# Schematics.net
KiCad netlist of a schematic drawn in Altium Designer
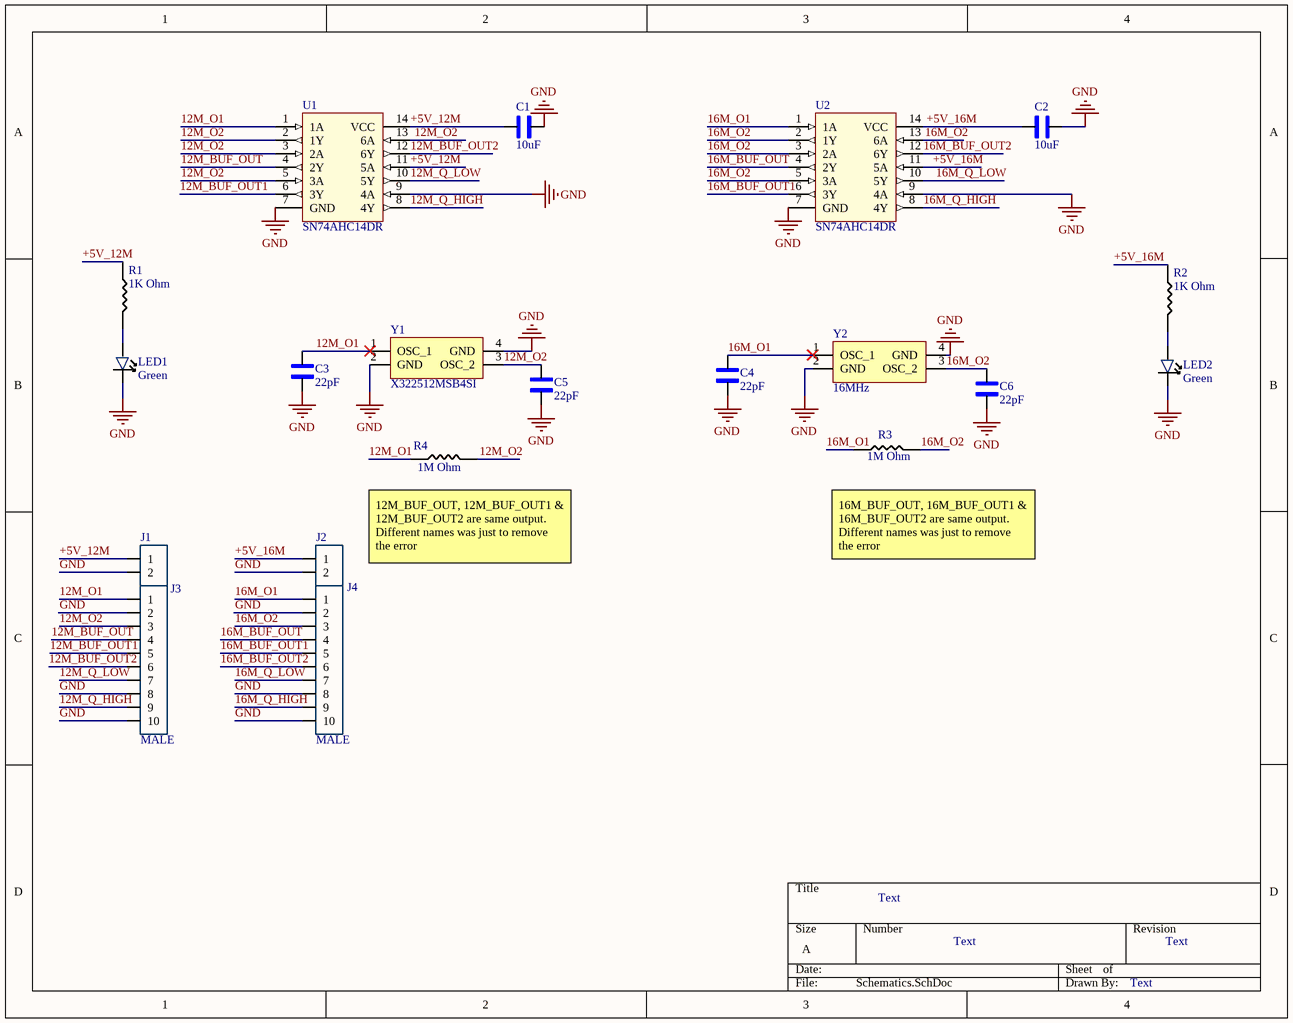
[diagram p0: Schematics.SchDoc]

(export (version "E")
  (design (tool "Eeschema 10.0.6"))
  (components
    (comp (ref "C1")
      (value "10uF")
      (footprint "0402_Passive_Capacitor")
      (description "10uF ±20% 6.3V X5R 0402 Multilayer Ceramic Capacitors MLCC - SMD/SMT RoHS")
      (fields (field (name "MFR PART #") "CL05A106MQ5NUNC") (field (name "LCSC PART#") "C15525"))
      (libsource (lib "ECEN5730Lib_JLC_2022_10") (part "C_10uF_0402"))
    )
    (comp (ref "C2")
      (value "10uF")
      (footprint "0402_Passive_Capacitor")
      (description "10uF ±20% 6.3V X5R 0402 Multilayer Ceramic Capacitors MLCC - SMD/SMT RoHS")
      (fields (field (name "MFR PART #") "CL05A106MQ5NUNC") (field (name "LCSC PART#") "C15525"))
      (libsource (lib "ECEN5730Lib_JLC_2022_10") (part "C_10uF_0402"))
    )
    (comp (ref "C3")
      (value "22pF")
      (footprint "0402_Passive_Capacitor")
      (description "MULTILAYER CERAMIC CAPACITORS MLCC - SMD/SMT 22PF 50V 0402 ROHS")
      (fields (field (name "MFR PART #") "0402CG220J500NT") (field (name "LCSC PART#") "C1555"))
      (libsource (lib "ECEN5730Lib_JLC_2022_10") (part "C_22pF_0402"))
    )
    (comp (ref "C4")
      (value "22pF")
      (footprint "0402_Passive_Capacitor")
      (description "MULTILAYER CERAMIC CAPACITORS MLCC - SMD/SMT 22PF 50V 0402 ROHS")
      (fields (field (name "MFR PART #") "0402CG220J500NT") (field (name "LCSC PART#") "C1555"))
      (libsource (lib "ECEN5730Lib_JLC_2022_10") (part "C_22pF_0402"))
    )
    (comp (ref "C5")
      (value "22pF")
      (footprint "0402_Passive_Capacitor")
      (description "MULTILAYER CERAMIC CAPACITORS MLCC - SMD/SMT 22PF 50V 0402 ROHS")
      (fields (field (name "MFR PART #") "0402CG220J500NT") (field (name "LCSC PART#") "C1555"))
      (libsource (lib "ECEN5730Lib_JLC_2022_10") (part "C_22pF_0402"))
    )
    (comp (ref "C6")
      (value "22pF")
      (footprint "0402_Passive_Capacitor")
      (description "MULTILAYER CERAMIC CAPACITORS MLCC - SMD/SMT 22PF 50V 0402 ROHS")
      (fields (field (name "MFR PART #") "0402CG220J500NT") (field (name "LCSC PART#") "C1555"))
      (libsource (lib "ECEN5730Lib_JLC_2022_10") (part "C_22pF_0402"))
    )
    (comp (ref "J1")
      (value "2 PIN")
      (footprint "2_PIN_100MIL")
      (description "2.54mm Straight 2 1 Header，Breakaway Through Hole,P=2.54mm Pin Header & Female Header ROHS")
      (fields (field (name "LCSC PART#") "C124375") (field (name "MFR PART #") "B-2100S02P-A110"))
      (libsource (lib "ECEN5730Lib_JLC_2022_10") (part "J_2_PIN_HEADER"))
    )
    (comp (ref "J2")
      (value "2 PIN")
      (footprint "2_PIN_100MIL")
      (description "2.54mm Straight 2 1 Header，Breakaway Through Hole,P=2.54mm Pin Header & Female Header ROHS")
      (fields (field (name "LCSC PART#") "C124375") (field (name "MFR PART #") "B-2100S02P-A110"))
      (libsource (lib "ECEN5730Lib_JLC_2022_10") (part "J_2_PIN_HEADER"))
    )
    (comp (ref "J3")
      (value "MALE")
      (footprint "10_PIN_100MIL")
      (fields (field (name "LCSC PART#") "C124372") (field (name "Comment") "MALE 10PIN"))
      (libsource (lib "ECEN5730Lib_JLC_2022_10") (part "JF_10_PIN_MALE"))
    )
    (comp (ref "J4")
      (value "MALE")
      (footprint "10_PIN_100MIL")
      (fields (field (name "LCSC PART#") "C124372") (field (name "Comment") "MALE 10PIN"))
      (libsource (lib "ECEN5730Lib_JLC_2022_10") (part "JF_10_PIN_MALE"))
    )
    (comp (ref "LED1")
      (value "Green")
      (footprint "LED_0603")
      (description "LIGHT EMITTING DIODES (LED) GREEN 520~535NM 112~258MCD@20MA TOP VIEW 0603 ROHS")
      (fields (field (name "MFR PART #") "19-217/GHC-YR1S2/3T") (field (name "LCSC PART#") "C72043"))
      (libsource (lib "ECEN5730Lib_JLC_2022_10") (part "LED_GREEN_0603"))
    )
    (comp (ref "LED2")
      (value "Green")
      (footprint "LED_0603")
      (description "LIGHT EMITTING DIODES (LED) GREEN 520~535NM 112~258MCD@20MA TOP VIEW 0603 ROHS")
      (fields (field (name "MFR PART #") "19-217/GHC-YR1S2/3T") (field (name "LCSC PART#") "C72043"))
      (libsource (lib "ECEN5730Lib_JLC_2022_10") (part "LED_GREEN_0603"))
    )
    (comp (ref "R1")
      (value "1K Ohm")
      (footprint "0402_Passive_Resistor")
      (description "1 kOhms chip resistor SURFACE MOUNT 1KOHMS ±1% 1/16W 0402 ROHS")
      (fields (field (name "MFR PART #") "0402WGF1001TCE") (field (name "LCSC PART#") "C11702"))
      (libsource (lib "ECEN5730Lib_JLC_2022_10") (part "R_1K_0402"))
    )
    (comp (ref "R2")
      (value "1K Ohm")
      (footprint "0402_Passive_Resistor")
      (description "1 kOhms chip resistor SURFACE MOUNT 1KOHMS ±1% 1/16W 0402 ROHS")
      (fields (field (name "MFR PART #") "0402WGF1001TCE") (field (name "LCSC PART#") "C11702"))
      (libsource (lib "ECEN5730Lib_JLC_2022_10") (part "R_1K_0402"))
    )
    (comp (ref "R3")
      (value "1M Ohm")
      (footprint "0402_Passive_Resistor")
      (description "CHIP RESISTOR - SURFACE MOUNT 1MOHMS ±1% 1/16W 0402 ROHS")
      (fields (field (name "MFR PART #") "0402WGF1004TCE") (field (name "LCSC PART#") "C26083"))
      (libsource (lib "ECEN5730Lib_JLC_2022_10") (part "R_1M_0402"))
    )
    (comp (ref "R4")
      (value "1M Ohm")
      (footprint "0402_Passive_Resistor")
      (description "CHIP RESISTOR - SURFACE MOUNT 1MOHMS ±1% 1/16W 0402 ROHS")
      (fields (field (name "MFR PART #") "0402WGF1004TCE") (field (name "LCSC PART#") "C26083"))
      (libsource (lib "ECEN5730Lib_JLC_2022_10") (part "R_1M_0402"))
    )
    (comp (ref "U1")
      (value "SN74AHC14DR")
      (footprint "SOIC127P600X175-14N")
      (description "6-ch, 2-V to 5.5-V inverters with Schmitt-Trigger inputs")
      (fields (field (name "MF") "Texas Instruments"))
      (libsource (lib "Hex_Inverter_Libraray") (part "SN74AHC14DR"))
    )
    (comp (ref "U2")
      (value "SN74AHC14DR")
      (footprint "SOIC127P600X175-14N")
      (description "6-ch, 2-V to 5.5-V inverters with Schmitt-Trigger inputs")
      (fields (field (name "MF") "Texas Instruments"))
      (libsource (lib "Hex_Inverter_Libraray") (part "SN74AHC14DR"))
    )
    (comp (ref "Y1")
      (value "X322512MSB4SI")
      (footprint "Crystal resonator")
      (description "SMD Crystal Resonators 12MHz ±10ppm SMD-3225_4P RoHS")
      (fields (field (name "LCSC PART#") "C9002"))
      (libsource (lib "ECEN5730Lib_JLC_2022_10") (part "X_12MHz_Res"))
    )
    (comp (ref "Y2")
      (value "16MHz")
      (footprint "Crystal resonator")
      (description "±10ppm 16000000Hz -40℃~85℃ 贴片无源晶振 60Ω 9pF SMD3225-4P Crystals ROHS")
      (fields (field (name "LCSC PART#") "C13738") (field (name "MFR PART #") "X322516MLB4SI"))
      (libsource (lib "ECEN5730Lib_JLC_2022_10") (part "X_16Mhz_Res"))
    )
  )
  (nets
    (net (code "1") (name "/+5V_12M") (class "Default")
      (node (ref "C1") (pin "1") (pinfunction "1_1") (pintype "passive"))
      (node (ref "J1") (pin "1") (pinfunction "1_1") (pintype "passive"))
      (node (ref "R1") (pin "1") (pinfunction "1_1") (pintype "passive"))
      (node (ref "U1") (pin "11") (pinfunction "5A_11") (pintype "input"))
      (node (ref "U1") (pin "14") (pinfunction "VCC_14") (pintype "power_in"))
    )
    (net (code "2") (name "/+5V_16M") (class "Default")
      (node (ref "C2") (pin "1") (pinfunction "1_1") (pintype "passive"))
      (node (ref "J2") (pin "1") (pinfunction "1_1") (pintype "passive"))
      (node (ref "R2") (pin "1") (pinfunction "1_1") (pintype "passive"))
      (node (ref "U2") (pin "11") (pinfunction "5A_11") (pintype "input"))
      (node (ref "U2") (pin "14") (pinfunction "VCC_14") (pintype "power_in"))
    )
    (net (code "3") (name "/12M_BUF_OUT") (class "Default")
      (node (ref "J3") (pin "4") (pinfunction "4_4") (pintype "passive"))
      (node (ref "U1") (pin "4") (pinfunction "2Y_4") (pintype "output"))
    )
    (net (code "4") (name "/12M_BUF_OUT1") (class "Default")
      (node (ref "J3") (pin "5") (pinfunction "5_5") (pintype "passive"))
      (node (ref "U1") (pin "6") (pinfunction "3Y_6") (pintype "output"))
    )
    (net (code "5") (name "/12M_BUF_OUT2") (class "Default")
      (node (ref "J3") (pin "6") (pinfunction "6_6") (pintype "passive"))
      (node (ref "U1") (pin "12") (pinfunction "6Y_12") (pintype "output"))
    )
    (net (code "6") (name "/12M_O1") (class "Default")
      (node (ref "C3") (pin "2") (pinfunction "2_2") (pintype "passive"))
      (node (ref "J3") (pin "1") (pinfunction "1_1") (pintype "passive"))
      (node (ref "R4") (pin "1") (pinfunction "1_1") (pintype "passive"))
      (node (ref "U1") (pin "1") (pinfunction "1A_1") (pintype "input"))
      (node (ref "Y1") (pin "1") (pinfunction "OSC_1_1") (pintype "passive"))
    )
    (net (code "7") (name "/12M_O2") (class "Default")
      (node (ref "C5") (pin "2") (pinfunction "2_2") (pintype "passive"))
      (node (ref "J3") (pin "3") (pinfunction "3_3") (pintype "passive"))
      (node (ref "R4") (pin "2") (pinfunction "2_2") (pintype "passive"))
      (node (ref "U1") (pin "13") (pinfunction "6A_13") (pintype "input"))
      (node (ref "U1") (pin "2") (pinfunction "1Y_2") (pintype "output"))
      (node (ref "U1") (pin "3") (pinfunction "2A_3") (pintype "input"))
      (node (ref "U1") (pin "5") (pinfunction "3A_5") (pintype "input"))
      (node (ref "Y1") (pin "3") (pinfunction "OSC_2_3") (pintype "passive"))
    )
    (net (code "8") (name "/12M_Q_HIGH") (class "Default")
      (node (ref "J3") (pin "9") (pinfunction "9_9") (pintype "passive"))
      (node (ref "U1") (pin "8") (pinfunction "4Y_8") (pintype "output"))
    )
    (net (code "9") (name "/12M_Q_LOW") (class "Default")
      (node (ref "J3") (pin "7") (pinfunction "7_7") (pintype "passive"))
      (node (ref "U1") (pin "10") (pinfunction "5Y_10") (pintype "output"))
    )
    (net (code "10") (name "/16M_BUF_OUT") (class "Default")
      (node (ref "J4") (pin "4") (pinfunction "4_4") (pintype "passive"))
      (node (ref "U2") (pin "4") (pinfunction "2Y_4") (pintype "output"))
    )
    (net (code "11") (name "/16M_BUF_OUT1") (class "Default")
      (node (ref "J4") (pin "5") (pinfunction "5_5") (pintype "passive"))
      (node (ref "U2") (pin "6") (pinfunction "3Y_6") (pintype "output"))
    )
    (net (code "12") (name "/16M_BUF_OUT2") (class "Default")
      (node (ref "J4") (pin "6") (pinfunction "6_6") (pintype "passive"))
      (node (ref "U2") (pin "12") (pinfunction "6Y_12") (pintype "output"))
    )
    (net (code "13") (name "/16M_O1") (class "Default")
      (node (ref "C4") (pin "2") (pinfunction "2_2") (pintype "passive"))
      (node (ref "J4") (pin "1") (pinfunction "1_1") (pintype "passive"))
      (node (ref "R3") (pin "1") (pinfunction "1_1") (pintype "passive"))
      (node (ref "U2") (pin "1") (pinfunction "1A_1") (pintype "input"))
      (node (ref "Y2") (pin "1") (pinfunction "OSC_1_1") (pintype "passive"))
    )
    (net (code "14") (name "/16M_O2") (class "Default")
      (node (ref "C6") (pin "2") (pinfunction "2_2") (pintype "passive"))
      (node (ref "J4") (pin "3") (pinfunction "3_3") (pintype "passive"))
      (node (ref "R3") (pin "2") (pinfunction "2_2") (pintype "passive"))
      (node (ref "U2") (pin "13") (pinfunction "6A_13") (pintype "input"))
      (node (ref "U2") (pin "2") (pinfunction "1Y_2") (pintype "output"))
      (node (ref "U2") (pin "3") (pinfunction "2A_3") (pintype "input"))
      (node (ref "U2") (pin "5") (pinfunction "3A_5") (pintype "input"))
      (node (ref "Y2") (pin "3") (pinfunction "OSC_2_3") (pintype "passive"))
    )
    (net (code "15") (name "/16M_Q_HIGH") (class "Default")
      (node (ref "J4") (pin "9") (pinfunction "9_9") (pintype "passive"))
      (node (ref "U2") (pin "8") (pinfunction "4Y_8") (pintype "output"))
    )
    (net (code "16") (name "/16M_Q_LOW") (class "Default")
      (node (ref "J4") (pin "7") (pinfunction "7_7") (pintype "passive"))
      (node (ref "U2") (pin "10") (pinfunction "5Y_10") (pintype "output"))
    )
    (net (code "17") (name "GND") (class "Default")
      (node (ref "C1") (pin "2") (pinfunction "2_2") (pintype "passive"))
      (node (ref "C2") (pin "2") (pinfunction "2_2") (pintype "passive"))
      (node (ref "C3") (pin "1") (pinfunction "1_1") (pintype "passive"))
      (node (ref "C4") (pin "1") (pinfunction "1_1") (pintype "passive"))
      (node (ref "C5") (pin "1") (pinfunction "1_1") (pintype "passive"))
      (node (ref "C6") (pin "1") (pinfunction "1_1") (pintype "passive"))
      (node (ref "J1") (pin "2") (pinfunction "2_2") (pintype "passive"))
      (node (ref "J2") (pin "2") (pinfunction "2_2") (pintype "passive"))
      (node (ref "J3") (pin "10") (pinfunction "10_10") (pintype "passive"))
      (node (ref "J3") (pin "2") (pinfunction "2_2") (pintype "passive"))
      (node (ref "J3") (pin "8") (pinfunction "8_8") (pintype "passive"))
      (node (ref "J4") (pin "10") (pinfunction "10_10") (pintype "passive"))
      (node (ref "J4") (pin "2") (pinfunction "2_2") (pintype "passive"))
      (node (ref "J4") (pin "8") (pinfunction "8_8") (pintype "passive"))
      (node (ref "LED1") (pin "2") (pinfunction "2_2") (pintype "passive"))
      (node (ref "LED2") (pin "2") (pinfunction "2_2") (pintype "passive"))
      (node (ref "U1") (pin "7") (pinfunction "GND_7") (pintype "power_in"))
      (node (ref "U1") (pin "9") (pinfunction "4A_9") (pintype "input"))
      (node (ref "U2") (pin "7") (pinfunction "GND_7") (pintype "power_in"))
      (node (ref "U2") (pin "9") (pinfunction "4A_9") (pintype "input"))
      (node (ref "Y1") (pin "2") (pinfunction "GND_2") (pintype "passive"))
      (node (ref "Y1") (pin "4") (pinfunction "GND_4") (pintype "passive"))
      (node (ref "Y2") (pin "2") (pinfunction "GND_2") (pintype "passive"))
      (node (ref "Y2") (pin "4") (pinfunction "GND_4") (pintype "passive"))
    )
    (net (code "18") (name "Net-(LED1-Pad1)") (class "Default")
      (node (ref "LED1") (pin "1") (pinfunction "1_1") (pintype "passive"))
      (node (ref "R1") (pin "2") (pinfunction "2_2") (pintype "passive"))
    )
    (net (code "19") (name "Net-(LED2-Pad1)") (class "Default")
      (node (ref "LED2") (pin "1") (pinfunction "1_1") (pintype "passive"))
      (node (ref "R2") (pin "2") (pinfunction "2_2") (pintype "passive"))
    )
  )
)
